# MCU.net
KiCad netlist of a schematic drawn in Altium Designer
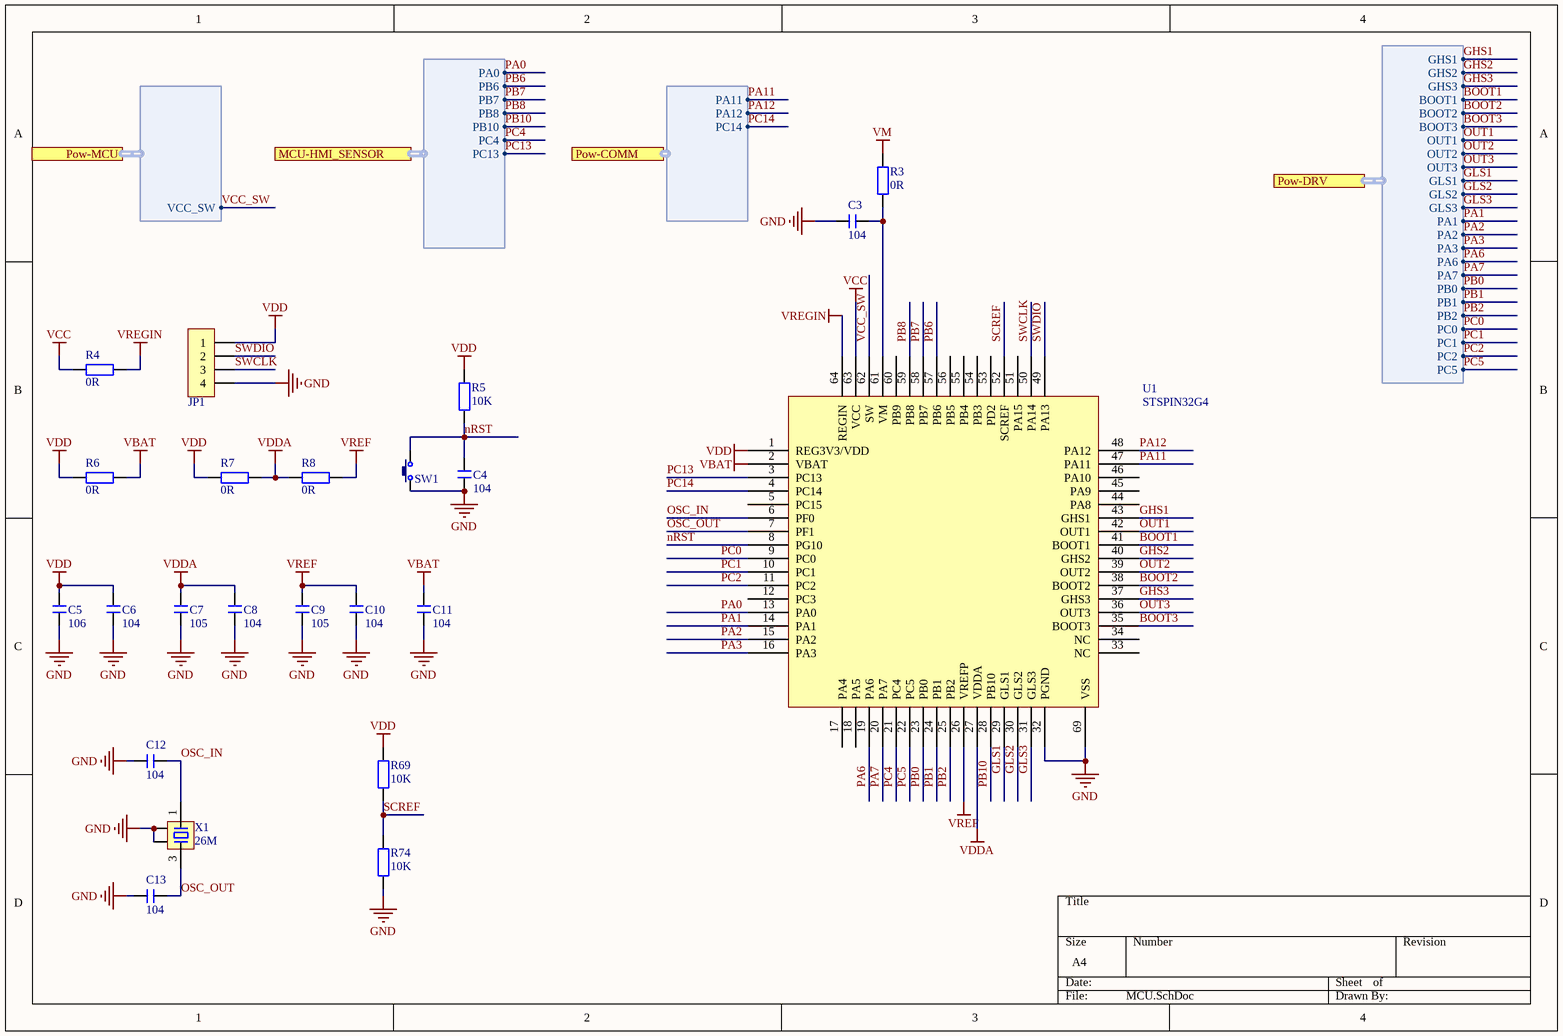
[diagram p0: MCU.SchDoc]

(export (version "E")
  (design (tool "Eeschema 10.0.6"))
  (components
    (comp (ref "C3")
      (value "104")
      (footprint "C 0603_L")
      (description "无极性贴片电容")
      (fields (field (name "版权归属") "源创客"))
      (libsource (lib "3.1   - 电阻-电容-电感") (part "C"))
    )
    (comp (ref "C4")
      (value "104")
      (footprint "C 0603_L")
      (description "无极性贴片电容")
      (fields (field (name "版权归属") "源创客"))
      (libsource (lib "3.1   - 电阻-电容-电感") (part "C"))
    )
    (comp (ref "C5")
      (value "106")
      (footprint "C 0805_L")
      (description "无极性贴片电容")
      (fields (field (name "版权归属") "源创客"))
      (libsource (lib "3.1   - 电阻-电容-电感") (part "C"))
    )
    (comp (ref "C6")
      (value "104")
      (footprint "C 0603_L")
      (description "无极性贴片电容")
      (fields (field (name "版权归属") "源创客"))
      (libsource (lib "3.1   - 电阻-电容-电感") (part "C"))
    )
    (comp (ref "C7")
      (value "105")
      (footprint "C 0603_L")
      (description "无极性贴片电容")
      (fields (field (name "版权归属") "源创客"))
      (libsource (lib "3.1   - 电阻-电容-电感") (part "C"))
    )
    (comp (ref "C8")
      (value "104")
      (footprint "C 0603_L")
      (description "无极性贴片电容")
      (fields (field (name "版权归属") "源创客"))
      (libsource (lib "3.1   - 电阻-电容-电感") (part "C"))
    )
    (comp (ref "C9")
      (value "105")
      (footprint "C 0603_L")
      (description "无极性贴片电容")
      (fields (field (name "版权归属") "源创客"))
      (libsource (lib "3.1   - 电阻-电容-电感") (part "C"))
    )
    (comp (ref "C10")
      (value "104")
      (footprint "C 0603_L")
      (description "无极性贴片电容")
      (fields (field (name "版权归属") "源创客"))
      (libsource (lib "3.1   - 电阻-电容-电感") (part "C"))
    )
    (comp (ref "C11")
      (value "104")
      (footprint "C 0603_L")
      (description "无极性贴片电容")
      (fields (field (name "版权归属") "源创客"))
      (libsource (lib "3.1   - 电阻-电容-电感") (part "C"))
    )
    (comp (ref "C12")
      (value "104")
      (footprint "C 0603_L")
      (description "无极性贴片电容")
      (fields (field (name "版权归属") "源创客"))
      (libsource (lib "3.1   - 电阻-电容-电感") (part "C"))
    )
    (comp (ref "C13")
      (value "104")
      (footprint "C 0603_L")
      (description "无极性贴片电容")
      (fields (field (name "版权归属") "源创客"))
      (libsource (lib "3.1   - 电阻-电容-电感") (part "C"))
    )
    (comp (ref "JP1")
      (value "HDR-1X4")
      (footprint "HDR2.54-LI-4P")
      (description "4P接插件")
      (fields (field (name "版权归属") "源创客"))
      (libsource (lib "4.5   - 接插件-脚距2.54") (part "Header 4"))
    )
    (comp (ref "R3")
      (value "0R")
      (footprint "R 0805_L")
      (description "贴片电阻")
      (fields (field (name "版权归属") "源创客"))
      (libsource (lib "3.1   - 电阻-电容-电感") (part "R"))
    )
    (comp (ref "R4")
      (value "0R")
      (footprint "R 0603_L")
      (description "贴片电阻")
      (fields (field (name "版权归属") "源创客"))
      (libsource (lib "3.1   - 电阻-电容-电感") (part "R"))
    )
    (comp (ref "R5")
      (value "10K")
      (footprint "R 0603_L")
      (description "贴片电阻")
      (fields (field (name "版权归属") "源创客"))
      (libsource (lib "3.1   - 电阻-电容-电感") (part "R"))
    )
    (comp (ref "R6")
      (value "0R")
      (footprint "R 0603_L")
      (description "贴片电阻")
      (fields (field (name "版权归属") "源创客"))
      (libsource (lib "3.1   - 电阻-电容-电感") (part "R"))
    )
    (comp (ref "R7")
      (value "0R")
      (footprint "R 0603_L")
      (description "贴片电阻")
      (fields (field (name "版权归属") "源创客"))
      (libsource (lib "3.1   - 电阻-电容-电感") (part "R"))
    )
    (comp (ref "R8")
      (value "0R")
      (footprint "R 0603_L")
      (description "贴片电阻")
      (fields (field (name "版权归属") "源创客"))
      (libsource (lib "3.1   - 电阻-电容-电感") (part "R"))
    )
    (comp (ref "R69")
      (value "10K")
      (footprint "R 0603_L")
      (description "贴片电阻")
      (fields (field (name "版权归属") "源创客"))
      (libsource (lib "3.1   - 电阻-电容-电感") (part "R"))
    )
    (comp (ref "R74")
      (value "10K")
      (footprint "R 0603_L")
      (description "贴片电阻")
      (fields (field (name "版权归属") "源创客"))
      (libsource (lib "3.1   - 电阻-电容-电感") (part "R"))
    )
    (comp (ref "SW1")
      (value "3x6x5")
      (footprint "TSW SMD-3*6*2.5")
      (description "3x6轻触开关")
      (fields (field (name "版权归属") "源创客"))
      (libsource (lib "5.1   - 按键-开关") (part "TSW 3x6"))
    )
    (comp (ref "U1")
      (value "STSPIN32G4")
      (footprint "QFN64 9x9_L")
      (libsource (lib "STSPIN32G4-Test-board") (part "STSPIN32G4"))
    )
    (comp (ref "X1")
      (value "26M")
      (footprint "OSC 3225-4P")
      (description "4脚无源晶振")
      (fields (field (name "版权归属") "源创客"))
      (libsource (lib "10.1 - 保险丝-晶振") (part "XTAL-4P"))
    )
  )
  (nets
    (net (code "5") (name "/BOOT1") (class "Default")
      (node (ref "U1") (pin "41") (pinfunction "BOOT1_41") (pintype "passive"))
    )
    (net (code "6") (name "/BOOT2") (class "Default")
      (node (ref "U1") (pin "38") (pinfunction "BOOT2_38") (pintype "passive"))
    )
    (net (code "7") (name "/BOOT3") (class "Default")
      (node (ref "U1") (pin "35") (pinfunction "BOOT3_35") (pintype "passive"))
    )
    (net (code "8") (name "/GHS1") (class "Default")
      (node (ref "U1") (pin "43") (pinfunction "GHS1_43") (pintype "passive"))
    )
    (net (code "9") (name "/GHS2") (class "Default")
      (node (ref "U1") (pin "40") (pinfunction "GHS2_40") (pintype "passive"))
    )
    (net (code "10") (name "/GHS3") (class "Default")
      (node (ref "U1") (pin "37") (pinfunction "GHS3_37") (pintype "passive"))
    )
    (net (code "11") (name "/GLS1") (class "Default")
      (node (ref "U1") (pin "29") (pinfunction "GLS1_29") (pintype "passive"))
    )
    (net (code "12") (name "/GLS2") (class "Default")
      (node (ref "U1") (pin "30") (pinfunction "GLS2_30") (pintype "passive"))
    )
    (net (code "13") (name "/GLS3") (class "Default")
      (node (ref "U1") (pin "31") (pinfunction "GLS3_31") (pintype "passive"))
    )
    (net (code "14") (name "/OSC_IN") (class "Default")
      (node (ref "C12") (pin "1") (pinfunction "1_1") (pintype "passive"))
      (node (ref "U1") (pin "6") (pinfunction "PF0_6") (pintype "passive"))
      (node (ref "X1") (pin "1") (pinfunction "1_1") (pintype "passive"))
    )
    (net (code "15") (name "/OSC_OUT") (class "Default")
      (node (ref "C13") (pin "1") (pinfunction "1_1") (pintype "passive"))
      (node (ref "U1") (pin "7") (pinfunction "PF1_7") (pintype "passive"))
      (node (ref "X1") (pin "3") (pinfunction "3_3") (pintype "passive"))
    )
    (net (code "16") (name "/OUT1") (class "Default")
      (node (ref "U1") (pin "42") (pinfunction "OUT1_42") (pintype "passive"))
    )
    (net (code "17") (name "/OUT2") (class "Default")
      (node (ref "U1") (pin "39") (pinfunction "OUT2_39") (pintype "passive"))
    )
    (net (code "18") (name "/OUT3") (class "Default")
      (node (ref "U1") (pin "36") (pinfunction "OUT3_36") (pintype "passive"))
    )
    (net (code "19") (name "/PA0") (class "Default")
      (node (ref "U1") (pin "13") (pinfunction "PA0_13") (pintype "passive"))
    )
    (net (code "20") (name "/PA1") (class "Default")
      (node (ref "U1") (pin "14") (pinfunction "PA1_14") (pintype "passive"))
    )
    (net (code "21") (name "/PA2") (class "Default")
      (node (ref "U1") (pin "15") (pinfunction "PA2_15") (pintype "passive"))
    )
    (net (code "22") (name "/PA3") (class "Default")
      (node (ref "U1") (pin "16") (pinfunction "PA3_16") (pintype "passive"))
    )
    (net (code "23") (name "/PA6") (class "Default")
      (node (ref "U1") (pin "19") (pinfunction "PA6_19") (pintype "passive"))
    )
    (net (code "24") (name "/PA7") (class "Default")
      (node (ref "U1") (pin "20") (pinfunction "PA7_20") (pintype "passive"))
    )
    (net (code "25") (name "/PA11") (class "Default")
      (node (ref "U1") (pin "47") (pinfunction "PA11_47") (pintype "passive"))
    )
    (net (code "26") (name "/PA12") (class "Default")
      (node (ref "U1") (pin "48") (pinfunction "PA12_48") (pintype "passive"))
    )
    (net (code "27") (name "/PB0") (class "Default")
      (node (ref "U1") (pin "23") (pinfunction "PB0_23") (pintype "passive"))
    )
    (net (code "28") (name "/PB1") (class "Default")
      (node (ref "U1") (pin "24") (pinfunction "PB1_24") (pintype "passive"))
    )
    (net (code "29") (name "/PB2") (class "Default")
      (node (ref "U1") (pin "25") (pinfunction "PB2_25") (pintype "passive"))
    )
    (net (code "30") (name "/PB6") (class "Default")
      (node (ref "U1") (pin "57") (pinfunction "PB6_57") (pintype "passive"))
    )
    (net (code "31") (name "/PB7") (class "Default")
      (node (ref "U1") (pin "58") (pinfunction "PB7_58") (pintype "passive"))
    )
    (net (code "32") (name "/PB8") (class "Default")
      (node (ref "U1") (pin "59") (pinfunction "PB8_59") (pintype "passive"))
    )
    (net (code "33") (name "/PB10") (class "Default")
      (node (ref "U1") (pin "28") (pinfunction "PB10_28") (pintype "passive"))
    )
    (net (code "34") (name "/PC0") (class "Default")
      (node (ref "U1") (pin "9") (pinfunction "PC0_9") (pintype "passive"))
    )
    (net (code "35") (name "/PC1") (class "Default")
      (node (ref "U1") (pin "10") (pinfunction "PC1_10") (pintype "passive"))
    )
    (net (code "36") (name "/PC2") (class "Default")
      (node (ref "U1") (pin "11") (pinfunction "PC2_11") (pintype "passive"))
    )
    (net (code "37") (name "/PC4") (class "Default")
      (node (ref "U1") (pin "21") (pinfunction "PC4_21") (pintype "passive"))
    )
    (net (code "38") (name "/PC5") (class "Default")
      (node (ref "U1") (pin "22") (pinfunction "PC5_22") (pintype "passive"))
    )
    (net (code "39") (name "/PC13") (class "Default")
      (node (ref "U1") (pin "3") (pinfunction "PC13_3") (pintype "passive"))
    )
    (net (code "40") (name "/PC14") (class "Default")
      (node (ref "U1") (pin "4") (pinfunction "PC14_4") (pintype "passive"))
    )
    (net (code "41") (name "/SCREF") (class "Default")
      (node (ref "R69") (pin "1") (pinfunction "1_1") (pintype "passive"))
      (node (ref "R74") (pin "2") (pinfunction "2_2") (pintype "passive"))
      (node (ref "U1") (pin "52") (pinfunction "SCREF_52") (pintype "passive"))
    )
    (net (code "42") (name "/SWCLK") (class "Default")
      (node (ref "JP1") (pin "3") (pinfunction "3_3") (pintype "passive"))
      (node (ref "U1") (pin "50") (pinfunction "PA14_50") (pintype "passive"))
    )
    (net (code "43") (name "/SWDIO") (class "Default")
      (node (ref "JP1") (pin "2") (pinfunction "2_2") (pintype "passive"))
      (node (ref "U1") (pin "49") (pinfunction "PA13_49") (pintype "passive"))
    )
    (net (code "44") (name "/VCC_SW") (class "Default")
      (node (ref "U1") (pin "62") (pinfunction "SW_62") (pintype "passive"))
    )
    (net (code "45") (name "/nRST") (class "Default")
      (node (ref "C4") (pin "2") (pinfunction "2_2") (pintype "passive"))
      (node (ref "R5") (pin "1") (pinfunction "1_1") (pintype "passive"))
      (node (ref "SW1") (pin "2") (pinfunction "2_2") (pintype "passive"))
      (node (ref "U1") (pin "8") (pinfunction "PG10_8") (pintype "passive"))
    )
    (net (code "50") (name "GND") (class "Default")
      (node (ref "C10") (pin "1") (pinfunction "1_1") (pintype "passive"))
      (node (ref "C11") (pin "1") (pinfunction "1_1") (pintype "passive"))
      (node (ref "C12") (pin "2") (pinfunction "2_2") (pintype "passive"))
      (node (ref "C13") (pin "2") (pinfunction "2_2") (pintype "passive"))
      (node (ref "C3") (pin "1") (pinfunction "1_1") (pintype "passive"))
      (node (ref "C4") (pin "1") (pinfunction "1_1") (pintype "passive"))
      (node (ref "C5") (pin "1") (pinfunction "1_1") (pintype "passive"))
      (node (ref "C6") (pin "1") (pinfunction "1_1") (pintype "passive"))
      (node (ref "C7") (pin "1") (pinfunction "1_1") (pintype "passive"))
      (node (ref "C8") (pin "1") (pinfunction "1_1") (pintype "passive"))
      (node (ref "C9") (pin "1") (pinfunction "1_1") (pintype "passive"))
      (node (ref "JP1") (pin "4") (pinfunction "4_4") (pintype "passive"))
      (node (ref "R74") (pin "1") (pinfunction "1_1") (pintype "passive"))
      (node (ref "SW1") (pin "1") (pinfunction "1_1") (pintype "passive"))
      (node (ref "U1") (pin "32") (pinfunction "PGND_32") (pintype "passive"))
      (node (ref "U1") (pin "69") (pinfunction "VSS_69") (pintype "passive"))
      (node (ref "X1") (pin "2") (pinfunction "2_2") (pintype "passive"))
      (node (ref "X1") (pin "4") (pinfunction "4_4") (pintype "passive"))
    )
    (net (code "51") (name "Net-(U1-VM)") (class "Default")
      (node (ref "C3") (pin "2") (pinfunction "2_2") (pintype "passive"))
      (node (ref "R3") (pin "1") (pinfunction "1_1") (pintype "passive"))
      (node (ref "U1") (pin "61") (pinfunction "VM_61") (pintype "passive"))
    )
    (net (code "52") (name "VBAT") (class "Default")
      (node (ref "C11") (pin "2") (pinfunction "2_2") (pintype "passive"))
      (node (ref "R6") (pin "1") (pinfunction "1_1") (pintype "passive"))
      (node (ref "U1") (pin "2") (pinfunction "VBAT_2") (pintype "passive"))
    )
    (net (code "53") (name "VCC") (class "Default")
      (node (ref "R4") (pin "2") (pinfunction "2_2") (pintype "passive"))
      (node (ref "U1") (pin "63") (pinfunction "VCC_63") (pintype "passive"))
    )
    (net (code "54") (name "VDD") (class "Default")
      (node (ref "C5") (pin "2") (pinfunction "2_2") (pintype "passive"))
      (node (ref "C6") (pin "2") (pinfunction "2_2") (pintype "passive"))
      (node (ref "JP1") (pin "1") (pinfunction "1_1") (pintype "passive"))
      (node (ref "R5") (pin "2") (pinfunction "2_2") (pintype "passive"))
      (node (ref "R6") (pin "2") (pinfunction "2_2") (pintype "passive"))
      (node (ref "R69") (pin "2") (pinfunction "2_2") (pintype "passive"))
      (node (ref "R7") (pin "2") (pinfunction "2_2") (pintype "passive"))
      (node (ref "U1") (pin "1") (pinfunction "REG3V3/VDD_1") (pintype "passive"))
    )
    (net (code "55") (name "VDDA") (class "Default")
      (node (ref "C7") (pin "2") (pinfunction "2_2") (pintype "passive"))
      (node (ref "C8") (pin "2") (pinfunction "2_2") (pintype "passive"))
      (node (ref "R7") (pin "1") (pinfunction "1_1") (pintype "passive"))
      (node (ref "R8") (pin "2") (pinfunction "2_2") (pintype "passive"))
      (node (ref "U1") (pin "27") (pinfunction "VDDA_27") (pintype "passive"))
    )
    (net (code "56") (name "VM") (class "Default")
      (node (ref "R3") (pin "2") (pinfunction "2_2") (pintype "passive"))
    )
    (net (code "57") (name "VREF") (class "Default")
      (node (ref "C10") (pin "2") (pinfunction "2_2") (pintype "passive"))
      (node (ref "C9") (pin "2") (pinfunction "2_2") (pintype "passive"))
      (node (ref "R8") (pin "1") (pinfunction "1_1") (pintype "passive"))
      (node (ref "U1") (pin "26") (pinfunction "VREFP_26") (pintype "passive"))
    )
    (net (code "58") (name "VREGIN") (class "Default")
      (node (ref "R4") (pin "1") (pinfunction "1_1") (pintype "passive"))
      (node (ref "U1") (pin "64") (pinfunction "REGIN_64") (pintype "passive"))
    )
    (net (code "59") (name "unconnected-(U1-NC-Pad33)") (class "Default")
      (node (ref "U1") (pin "33") (pinfunction "NC_33") (pintype "passive"))
    )
    (net (code "60") (name "unconnected-(U1-NC-Pad34)") (class "Default")
      (node (ref "U1") (pin "34") (pinfunction "NC_34") (pintype "passive"))
    )
    (net (code "61") (name "unconnected-(U1-PA4-Pad17)") (class "Default")
      (node (ref "U1") (pin "17") (pinfunction "PA4_17") (pintype "passive"))
    )
    (net (code "62") (name "unconnected-(U1-PA5-Pad18)") (class "Default")
      (node (ref "U1") (pin "18") (pinfunction "PA5_18") (pintype "passive"))
    )
    (net (code "63") (name "unconnected-(U1-PA8-Pad44)") (class "Default")
      (node (ref "U1") (pin "44") (pinfunction "PA8_44") (pintype "passive"))
    )
    (net (code "64") (name "unconnected-(U1-PA9-Pad45)") (class "Default")
      (node (ref "U1") (pin "45") (pinfunction "PA9_45") (pintype "passive"))
    )
    (net (code "65") (name "unconnected-(U1-PA10-Pad46)") (class "Default")
      (node (ref "U1") (pin "46") (pinfunction "PA10_46") (pintype "passive"))
    )
    (net (code "66") (name "unconnected-(U1-PA15-Pad51)") (class "Default")
      (node (ref "U1") (pin "51") (pinfunction "PA15_51") (pintype "passive"))
    )
    (net (code "67") (name "unconnected-(U1-PB3-Pad54)") (class "Default")
      (node (ref "U1") (pin "54") (pinfunction "PB3_54") (pintype "passive"))
    )
    (net (code "68") (name "unconnected-(U1-PB4-Pad55)") (class "Default")
      (node (ref "U1") (pin "55") (pinfunction "PB4_55") (pintype "passive"))
    )
    (net (code "69") (name "unconnected-(U1-PB5-Pad56)") (class "Default")
      (node (ref "U1") (pin "56") (pinfunction "PB5_56") (pintype "passive"))
    )
    (net (code "70") (name "unconnected-(U1-PB9-Pad60)") (class "Default")
      (node (ref "U1") (pin "60") (pinfunction "PB9_60") (pintype "passive"))
    )
    (net (code "71") (name "unconnected-(U1-PC3-Pad12)") (class "Default")
      (node (ref "U1") (pin "12") (pinfunction "PC3_12") (pintype "passive"))
    )
    (net (code "72") (name "unconnected-(U1-PC15-Pad5)") (class "Default")
      (node (ref "U1") (pin "5") (pinfunction "PC15_5") (pintype "passive"))
    )
    (net (code "73") (name "unconnected-(U1-PD2-Pad53)") (class "Default")
      (node (ref "U1") (pin "53") (pinfunction "PD2_53") (pintype "passive"))
    )
  )
)
